# cliff_sensor.net
KiCad netlist of a schematic drawn in EAGLE
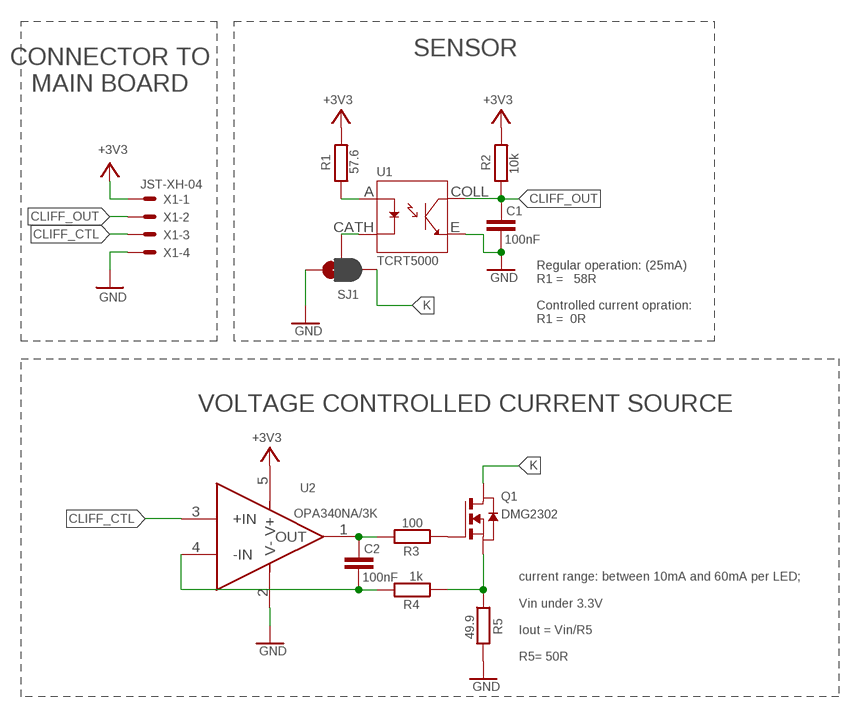
[diagram p0: schematic, sheet 1]

(export (version "E")
  (design (tool "Eeschema 10.0.6"))
  (components
    (comp (ref "C1")
      (value "100nF")
      (footprint "eagle-import:C0402")
      (libsource (lib "eagle-import") (part "C-EUC0402"))
    )
    (comp (ref "C2")
      (value "100nF")
      (footprint "eagle-import:C0402")
      (libsource (lib "eagle-import") (part "C-EUC0402"))
    )
    (comp (ref "Q1")
      (value "DMG2302")
      (footprint "eagle-import:SOT-23")
      (libsource (lib "eagle-import") (part "NMOS-SOT23"))
    )
    (comp (ref "R1")
      (value "57.6")
      (footprint "eagle-import:R0402")
      (libsource (lib "eagle-import") (part "R-EU_R0402"))
    )
    (comp (ref "R2")
      (value "10k")
      (footprint "eagle-import:R0402")
      (libsource (lib "eagle-import") (part "R-EU_R0402"))
    )
    (comp (ref "R3")
      (value "100")
      (footprint "eagle-import:R0402")
      (libsource (lib "eagle-import") (part "R-EU_R0402"))
    )
    (comp (ref "R4")
      (value "1k")
      (footprint "eagle-import:R0402")
      (libsource (lib "eagle-import") (part "R-EU_R0402"))
    )
    (comp (ref "R5")
      (value "49.9")
      (footprint "eagle-import:R0402")
      (libsource (lib "eagle-import") (part "R-EU_R0402"))
    )
    (comp (ref "SJ1")
      (value "SPARKFUN-PASSIVES_JUMPER_PAD-3-1&2_NC_BY_PASTE")
      (footprint "eagle-import:SPARKFUN-PASSIVES_PAD-HUMPER-3-1&2_NC_BY_PASTE_YES_SILK_FULL_BOX")
      (libsource (lib "eagle-import") (part "SPARKFUN-PASSIVES_JUMPER_PAD-3-1&2_NC_BY_PASTE"))
    )
    (comp (ref "U1")
      (value "TCRT5000")
      (footprint "eagle-import:OPTO_TCRT5000")
      (fields (field (name "MF") "Vishay"))
      (libsource (lib "eagle-import") (part "TCRT5000"))
    )
    (comp (ref "U2")
      (value "OPA340NA/3K")
      (footprint "eagle-import:SOT95P280X145-5N")
      (fields (field (name "MF") "Texas Instruments"))
      (libsource (lib "eagle-import") (part "OPA340NA/3K"))
    )
    (comp (ref "X1")
      (value "JST-XH-04")
      (footprint "eagle-import:JST-XH-04-PACKAGE-ROUND-PAD")
      (libsource (lib "eagle-import") (part "JST-XH-04-PIN-ROUND-PAD"))
    )
  )
  (nets
    (net (code "1") (name "+3V3") (class "Default")
      (node (ref "R1") (pin "2") (pinfunction "2_2") (pintype "passive"))
      (node (ref "R2") (pin "2") (pinfunction "2_2") (pintype "passive"))
      (node (ref "U2") (pin "5") (pinfunction "V+_5") (pintype "power_in"))
      (node (ref "X1") (pin "1") (pinfunction "S_1") (pintype "passive"))
    )
    (net (code "2") (name "CLIFF_CTL") (class "Default")
      (node (ref "U2") (pin "3") (pinfunction "+IN_3") (pintype "input"))
      (node (ref "X1") (pin "3") (pinfunction "S_3") (pintype "passive"))
    )
    (net (code "3") (name "CLIFF_OUT") (class "Default")
      (node (ref "C1") (pin "2") (pinfunction "2_2") (pintype "passive"))
      (node (ref "R2") (pin "1") (pinfunction "1_1") (pintype "passive"))
      (node (ref "U1") (pin "COLL") (pinfunction "COLL_COLL") (pintype "passive"))
      (node (ref "X1") (pin "2") (pinfunction "S_2") (pintype "passive"))
    )
    (net (code "4") (name "GND") (class "Default")
      (node (ref "C1") (pin "1") (pinfunction "1_1") (pintype "passive"))
      (node (ref "R5") (pin "2") (pinfunction "2_2") (pintype "passive"))
      (node (ref "SJ1") (pin "3") (pinfunction "3_3") (pintype "passive"))
      (node (ref "U1") (pin "E") (pinfunction "E_E") (pintype "passive"))
      (node (ref "U2") (pin "2") (pinfunction "V-_2") (pintype "power_in"))
      (node (ref "X1") (pin "4") (pinfunction "S_4") (pintype "passive"))
    )
    (net (code "5") (name "K") (class "Default")
      (node (ref "Q1") (pin "D") (pinfunction "D_D") (pintype "passive"))
      (node (ref "SJ1") (pin "1") (pinfunction "1_1") (pintype "passive"))
    )
    (net (code "6") (name "Net-(Q1-PadG)") (class "Default")
      (node (ref "Q1") (pin "G") (pinfunction "G_G") (pintype "passive"))
      (node (ref "R3") (pin "1") (pinfunction "1_1") (pintype "passive"))
    )
    (net (code "7") (name "Net-(Q1-PadS)") (class "Default")
      (node (ref "Q1") (pin "S") (pinfunction "S_S") (pintype "passive"))
      (node (ref "R4") (pin "1") (pinfunction "1_1") (pintype "passive"))
      (node (ref "R5") (pin "1") (pinfunction "1_1") (pintype "passive"))
    )
    (net (code "8") (name "Net-(R1-Pad1)") (class "Default")
      (node (ref "R1") (pin "1") (pinfunction "1_1") (pintype "passive"))
      (node (ref "U1") (pin "A") (pinfunction "A_A") (pintype "passive"))
    )
    (net (code "9") (name "Net-(SJ1-Pad2)") (class "Default")
      (node (ref "SJ1") (pin "2") (pinfunction "2_2") (pintype "passive"))
      (node (ref "U1") (pin "CATH") (pinfunction "CATH_CATH") (pintype "passive"))
    )
    (net (code "10") (name "Net-(U2--IN)") (class "Default")
      (node (ref "C2") (pin "1") (pinfunction "1_1") (pintype "passive"))
      (node (ref "R4") (pin "2") (pinfunction "2_2") (pintype "passive"))
      (node (ref "U2") (pin "4") (pinfunction "-IN_4") (pintype "input"))
    )
    (net (code "11") (name "Net-(U2-OUT)") (class "Default")
      (node (ref "C2") (pin "2") (pinfunction "2_2") (pintype "passive"))
      (node (ref "R3") (pin "2") (pinfunction "2_2") (pintype "passive"))
      (node (ref "U2") (pin "1") (pinfunction "OUT_1") (pintype "output"))
    )
  )
)
